# VCNL4040_IR_Finger_Sensor.net
KiCad netlist of a schematic drawn in EAGLE
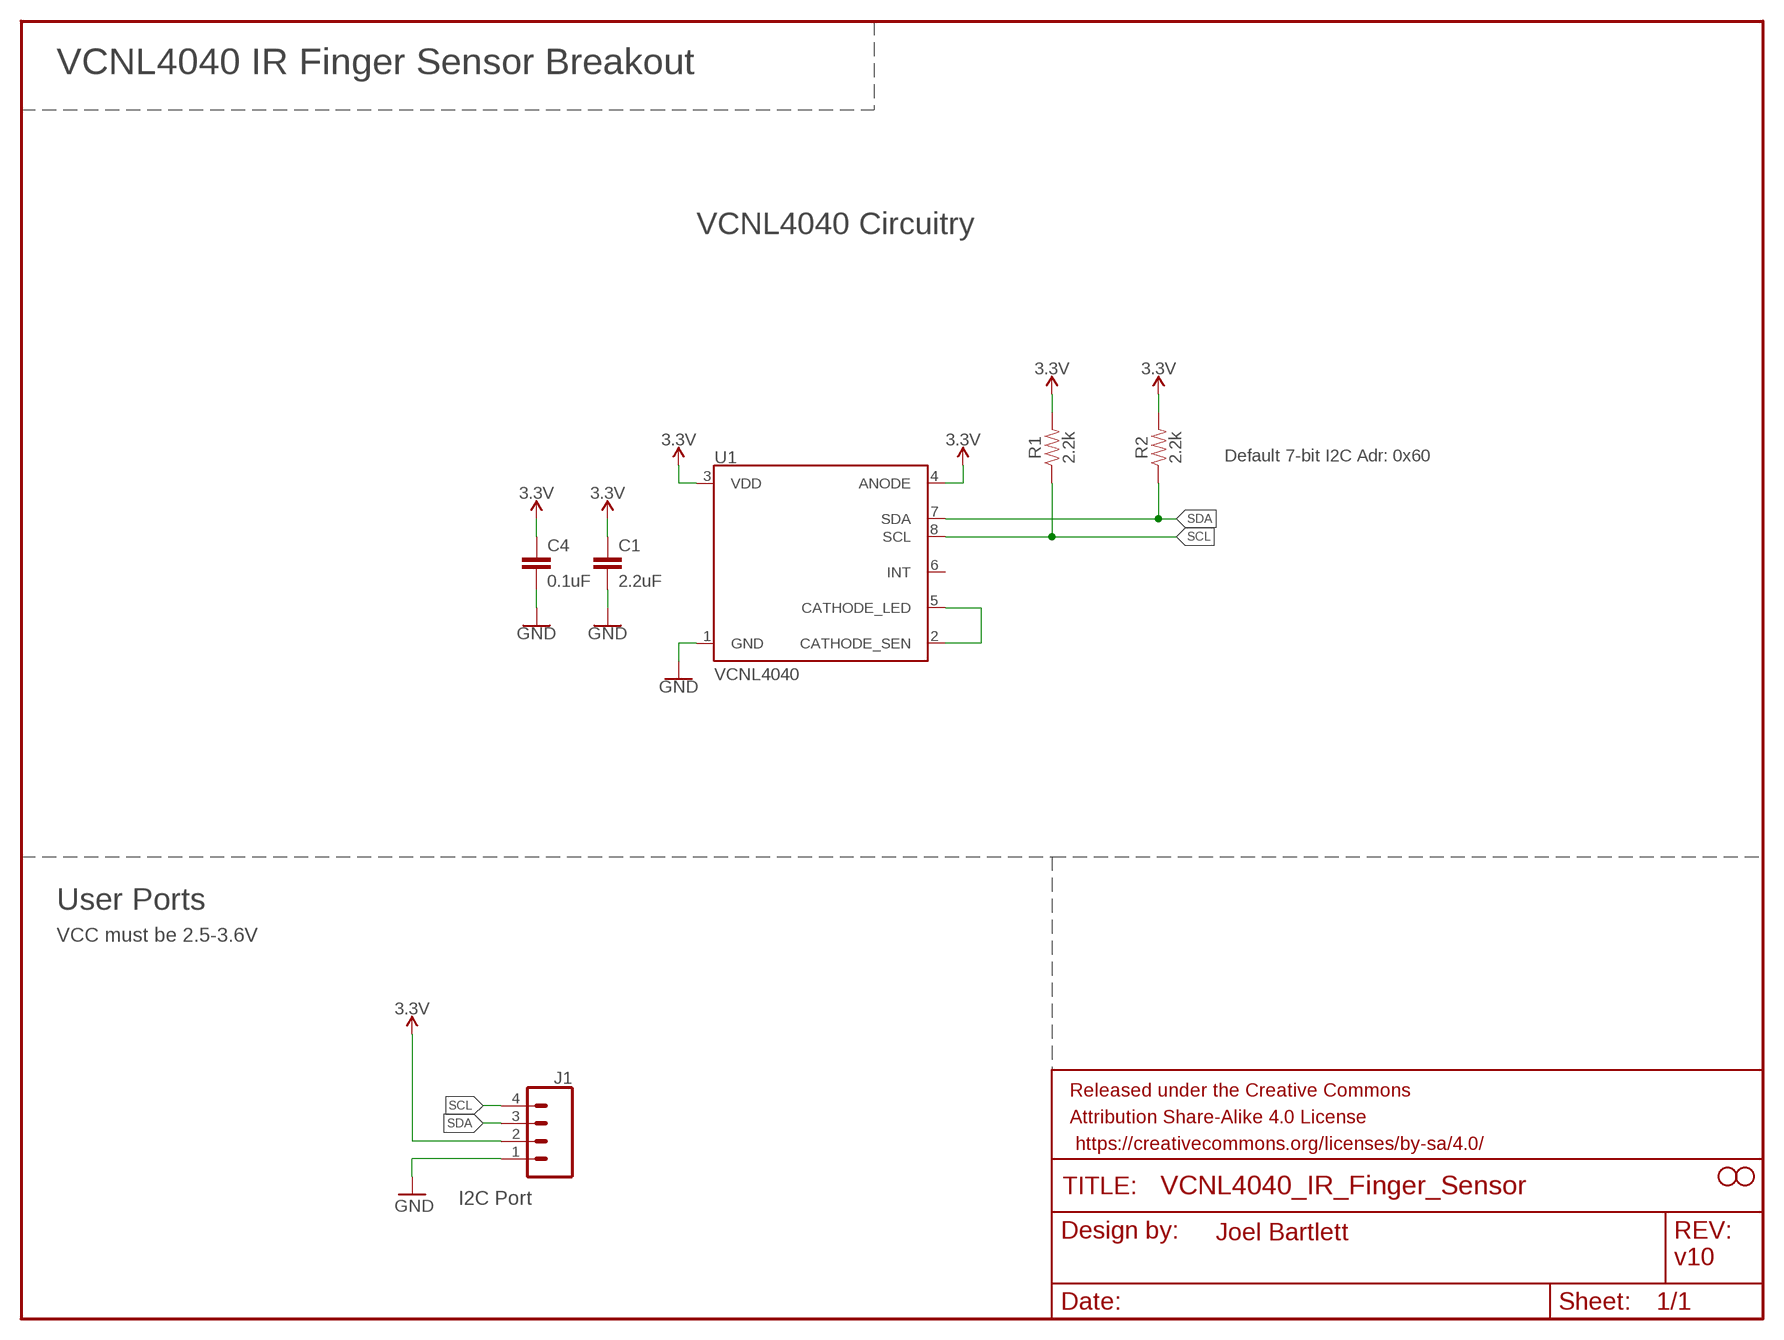
[diagram p0: schematic, sheet 1]

(export (version "E")
  (design (tool "Eeschema 10.0.6"))
  (components
    (comp (ref "C1")
      (value "2.2uF")
      (footprint "eagle-import:0603")
      (libsource (lib "eagle-import") (part "2.2UF-0603-10V-20%"))
    )
    (comp (ref "C4")
      (value "0.1uF")
      (footprint "eagle-import:0603")
      (libsource (lib "eagle-import") (part "0.1UF-0603-25V-(+80/-20%)"))
    )
    (comp (ref "FRAME2")
      (value "FRAME-LETTER")
      (footprint "eagle-import:CREATIVE_COMMONS")
      (libsource (lib "eagle-import") (part "FRAME-LETTER"))
    )
    (comp (ref "J1")
      (value "CONN_04SMD2")
      (footprint "eagle-import:1X04_1MM_RA")
      (libsource (lib "eagle-import") (part "CONN_04SMD2"))
    )
    (comp (ref "R1")
      (value "2.2k")
      (footprint "eagle-import:0603")
      (libsource (lib "eagle-import") (part "2.2KOHM-0603-1/10W-1%"))
    )
    (comp (ref "R2")
      (value "2.2k")
      (footprint "eagle-import:0603")
      (libsource (lib "eagle-import") (part "2.2KOHM-0603-1/10W-1%"))
    )
    (comp (ref "U$1")
      (value "STAND-OFF")
      (footprint "eagle-import:STAND-OFF-#2")
      (libsource (lib "eagle-import") (part "STAND-OFF"))
    )
    (comp (ref "U$2")
      (value "STAND-OFF")
      (footprint "eagle-import:STAND-OFF-#2")
      (libsource (lib "eagle-import") (part "STAND-OFF"))
    )
    (comp (ref "U1")
      (value "VCNL4040")
      (footprint "eagle-import:VCNL4040")
      (libsource (lib "eagle-import") (part "VCNL4040"))
    )
  )
  (nets
    (net (code "1") (name "3.3V") (class "Default")
      (node (ref "C1") (pin "1") (pinfunction "1_1") (pintype "passive"))
      (node (ref "C4") (pin "1") (pinfunction "1_1") (pintype "passive"))
      (node (ref "J1") (pin "2") (pinfunction "2_2") (pintype "passive"))
      (node (ref "R1") (pin "2") (pinfunction "2_2") (pintype "passive"))
      (node (ref "R2") (pin "2") (pinfunction "2_2") (pintype "passive"))
      (node (ref "U1") (pin "3") (pinfunction "VDD_3") (pintype "bidirectional"))
      (node (ref "U1") (pin "4") (pinfunction "ANODE_4") (pintype "bidirectional"))
    )
    (net (code "2") (name "GND") (class "Default")
      (node (ref "C1") (pin "2") (pinfunction "2_2") (pintype "passive"))
      (node (ref "C4") (pin "2") (pinfunction "2_2") (pintype "passive"))
      (node (ref "J1") (pin "1") (pinfunction "1_1") (pintype "passive"))
      (node (ref "U1") (pin "1") (pinfunction "GND_1") (pintype "bidirectional"))
    )
    (net (code "3") (name "Net-(U1-CATHODE_LED)") (class "Default")
      (node (ref "U1") (pin "2") (pinfunction "CATHODE_SEN_2") (pintype "bidirectional"))
      (node (ref "U1") (pin "5") (pinfunction "CATHODE_LED_5") (pintype "bidirectional"))
    )
    (net (code "4") (name "SCL") (class "Default")
      (node (ref "J1") (pin "4") (pinfunction "4_4") (pintype "passive"))
      (node (ref "R1") (pin "1") (pinfunction "1_1") (pintype "passive"))
      (node (ref "U1") (pin "8") (pinfunction "SCL_8") (pintype "bidirectional"))
    )
    (net (code "5") (name "SDA") (class "Default")
      (node (ref "J1") (pin "3") (pinfunction "3_3") (pintype "passive"))
      (node (ref "R2") (pin "1") (pinfunction "1_1") (pintype "passive"))
      (node (ref "U1") (pin "7") (pinfunction "SDA_7") (pintype "bidirectional"))
    )
    (net (code "6") (name "unconnected-(U1-INT-Pad6)") (class "Default")
      (node (ref "U1") (pin "6") (pinfunction "INT_6") (pintype "bidirectional"))
    )
  )
)
